# ESP-WiFi.net
KiCad netlist of a schematic drawn in Altium Designer
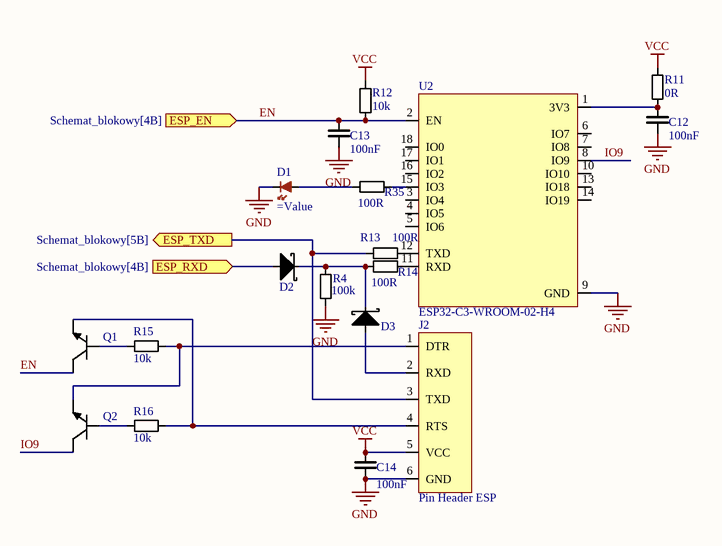
[diagram p0: ESP-WiFi.SchDoc]

(export (version "E")
  (design (tool "Eeschema 10.0.6"))
  (components
    (comp (ref "C12")
      (value "100nF")
      (footprint "0603_CAP")
      (description "Ceramic capacitor")
      (libsource (lib "Cap") (part "Cap"))
    )
    (comp (ref "C13")
      (value "100nF")
      (footprint "0603_CAP")
      (description "Ceramic capacitor")
      (libsource (lib "Cap") (part "Cap"))
    )
    (comp (ref "C14")
      (value "100nF")
      (footprint "0603_CAP")
      (description "Ceramic capacitor")
      (libsource (lib "Cap") (part "Cap"))
    )
    (comp (ref "D1")
      (value "~")
      (footprint "0603_LED_R_Reflow")
      (description "Red LED diode")
      (fields (field (name "PARTNUMBER") "APT1608SURC"))
      (libsource (lib "PBL4_GR4_SchLib") (part "LED_R_small"))
    )
    (comp (ref "D2")
      (value "~")
      (footprint "SOT23-R")
      (description "Schottky Diode")
      (fields (field (name "PARTNUMBER") "BAT54C"))
      (libsource (lib "Diodes") (part "D Schottky"))
    )
    (comp (ref "D3")
      (value "~")
      (footprint "SOT23-R")
      (description "Schottky Diode")
      (fields (field (name "PARTNUMBER") "BAT54C"))
      (libsource (lib "Diodes") (part "D Schottky"))
    )
    (comp (ref "J2")
      (value "Pin Header ESP")
      (footprint "SAMTEC_TSW-112-16-T-S-06")
      (libsource (lib "ESP32-C3-WROOM-02-H4") (part "Pin Header ESP"))
    )
    (comp (ref "Q1")
      (value "NPN")
      (footprint "SOT95P240X110-3N")
      (description "NPN General-purpose Transistor")
      (fields (field (name "PARTNUMBER") "BC848C-7-F"))
      (libsource (lib "NPN") (part "NPN"))
    )
    (comp (ref "Q2")
      (value "NPN")
      (footprint "SOT95P240X110-3N")
      (description "NPN General-purpose Transistor")
      (fields (field (name "PARTNUMBER") "BC848C-7-F"))
      (libsource (lib "NPN") (part "NPN"))
    )
    (comp (ref "R4")
      (value "100k")
      (footprint "0603_RES")
      (description "Resistor")
      (libsource (lib "RES") (part "RES"))
    )
    (comp (ref "R11")
      (value "0R")
      (footprint "0603_RES")
      (description "Resistor")
      (libsource (lib "RES") (part "RES"))
    )
    (comp (ref "R12")
      (value "10k")
      (footprint "0603_RES")
      (description "Resistor")
      (libsource (lib "RES") (part "RES"))
    )
    (comp (ref "R13")
      (value "100R")
      (footprint "0603_RES")
      (description "Resistor")
      (libsource (lib "RES") (part "RES"))
    )
    (comp (ref "R14")
      (value "100R")
      (footprint "0603_RES")
      (description "Resistor")
      (libsource (lib "RES") (part "RES"))
    )
    (comp (ref "R15")
      (value "10k")
      (footprint "0603_RES")
      (description "Resistor")
      (libsource (lib "RES") (part "RES"))
    )
    (comp (ref "R16")
      (value "10k")
      (footprint "0603_RES")
      (description "Resistor")
      (libsource (lib "RES") (part "RES"))
    )
    (comp (ref "R35")
      (value "100R")
      (footprint "0603_RES")
      (description "Resistor")
      (libsource (lib "RES") (part "RES"))
    )
    (comp (ref "U2")
      (value "ESP32-C3-WROOM-02-H4")
      (footprint "MODULE_ESP32-C3-WROOM-02-H4")
      (fields (field (name "MF") "Espressif Systems"))
      (libsource (lib "ESP32-C3-WROOM-02-H4") (part "ESP32-C3-WROOM-02-H4"))
    )
  )
  (nets
    (net (code "1") (name "/EN") (class "Default")
      (node (ref "C13") (pin "2") (pinfunction "2_2") (pintype "passive"))
      (node (ref "Q1") (pin "3") (pinfunction "C_3") (pintype "passive"))
      (node (ref "R12") (pin "1") (pinfunction "1_1") (pintype "passive"))
      (node (ref "U2") (pin "2") (pinfunction "EN_2") (pintype "passive"))
    )
    (net (code "2") (name "/ESP_RXD") (class "Default")
      (node (ref "D2") (pin "1") (pinfunction "A_1") (pintype "passive"))
    )
    (net (code "3") (name "/ESP_TXD") (class "Default")
      (node (ref "J2") (pin "3") (pinfunction "TXD_3") (pintype "passive"))
      (node (ref "R13") (pin "1") (pinfunction "1_1") (pintype "passive"))
    )
    (net (code "4") (name "/IO9") (class "Default")
      (node (ref "Q2") (pin "3") (pinfunction "C_3") (pintype "passive"))
      (node (ref "U2") (pin "8") (pinfunction "IO9_8") (pintype "passive"))
    )
    (net (code "5") (name "GND") (class "Default")
      (node (ref "C12") (pin "1") (pinfunction "1_1") (pintype "passive"))
      (node (ref "C13") (pin "1") (pinfunction "1_1") (pintype "passive"))
      (node (ref "C14") (pin "1") (pinfunction "1_1") (pintype "passive"))
      (node (ref "D1") (pin "2") (pinfunction "K_2") (pintype "passive"))
      (node (ref "J2") (pin "6") (pinfunction "GND_6") (pintype "passive"))
      (node (ref "R4") (pin "1") (pinfunction "1_1") (pintype "passive"))
      (node (ref "U2") (pin "9") (pinfunction "GND_9") (pintype "passive"))
    )
    (net (code "6") (name "Net-(D1-A)") (class "Default")
      (node (ref "D1") (pin "1") (pinfunction "A_1") (pintype "passive"))
      (node (ref "R35") (pin "1") (pinfunction "1_1") (pintype "passive"))
    )
    (net (code "7") (name "Net-(D2-K)") (class "Default")
      (node (ref "D2") (pin "3") (pinfunction "K_3") (pintype "passive"))
      (node (ref "D3") (pin "3") (pinfunction "K_3") (pintype "passive"))
      (node (ref "R14") (pin "1") (pinfunction "1_1") (pintype "passive"))
      (node (ref "R4") (pin "2") (pinfunction "2_2") (pintype "passive"))
    )
    (net (code "8") (name "Net-(D3-A)") (class "Default")
      (node (ref "D3") (pin "1") (pinfunction "A_1") (pintype "passive"))
      (node (ref "J2") (pin "2") (pinfunction "RXD_2") (pintype "passive"))
    )
    (net (code "9") (name "Net-(J2-DTR)") (class "Default")
      (node (ref "J2") (pin "1") (pinfunction "DTR_1") (pintype "passive"))
      (node (ref "Q2") (pin "2") (pinfunction "E_2") (pintype "passive"))
      (node (ref "R15") (pin "1") (pinfunction "1_1") (pintype "passive"))
    )
    (net (code "10") (name "Net-(J2-RTS)") (class "Default")
      (node (ref "J2") (pin "4") (pinfunction "RTS_4") (pintype "passive"))
      (node (ref "Q1") (pin "2") (pinfunction "E_2") (pintype "passive"))
      (node (ref "R16") (pin "1") (pinfunction "1_1") (pintype "passive"))
    )
    (net (code "11") (name "Net-(Q1-B)") (class "Default")
      (node (ref "Q1") (pin "1") (pinfunction "B_1") (pintype "passive"))
      (node (ref "R15") (pin "2") (pinfunction "2_2") (pintype "passive"))
    )
    (net (code "12") (name "Net-(Q2-B)") (class "Default")
      (node (ref "Q2") (pin "1") (pinfunction "B_1") (pintype "passive"))
      (node (ref "R16") (pin "2") (pinfunction "2_2") (pintype "passive"))
    )
    (net (code "13") (name "Net-(U2-3V3)") (class "Default")
      (node (ref "C12") (pin "2") (pinfunction "2_2") (pintype "passive"))
      (node (ref "R11") (pin "1") (pinfunction "1_1") (pintype "passive"))
      (node (ref "U2") (pin "1") (pinfunction "3V3_1") (pintype "passive"))
    )
    (net (code "14") (name "Net-(U2-IO3)") (class "Default")
      (node (ref "R35") (pin "2") (pinfunction "2_2") (pintype "passive"))
      (node (ref "U2") (pin "15") (pinfunction "IO3_15") (pintype "passive"))
    )
    (net (code "15") (name "Net-(U2-RXD)") (class "Default")
      (node (ref "R14") (pin "2") (pinfunction "2_2") (pintype "passive"))
      (node (ref "U2") (pin "11") (pinfunction "RXD_11") (pintype "passive"))
    )
    (net (code "16") (name "Net-(U2-TXD)") (class "Default")
      (node (ref "R13") (pin "2") (pinfunction "2_2") (pintype "passive"))
      (node (ref "U2") (pin "12") (pinfunction "TXD_12") (pintype "passive"))
    )
    (net (code "17") (name "VCC") (class "Default")
      (node (ref "C14") (pin "2") (pinfunction "2_2") (pintype "passive"))
      (node (ref "J2") (pin "5") (pinfunction "VCC_5") (pintype "passive"))
      (node (ref "R11") (pin "2") (pinfunction "2_2") (pintype "passive"))
      (node (ref "R12") (pin "2") (pinfunction "2_2") (pintype "passive"))
    )
    (net (code "18") (name "unconnected-(U2-IO0-Pad18)") (class "Default")
      (node (ref "U2") (pin "18") (pinfunction "IO0_18") (pintype "passive"))
    )
    (net (code "19") (name "unconnected-(U2-IO1-Pad17)") (class "Default")
      (node (ref "U2") (pin "17") (pinfunction "IO1_17") (pintype "passive"))
    )
    (net (code "20") (name "unconnected-(U2-IO2-Pad16)") (class "Default")
      (node (ref "U2") (pin "16") (pinfunction "IO2_16") (pintype "passive"))
    )
    (net (code "21") (name "unconnected-(U2-IO4-Pad3)") (class "Default")
      (node (ref "U2") (pin "3") (pinfunction "IO4_3") (pintype "passive"))
    )
    (net (code "22") (name "unconnected-(U2-IO5-Pad4)") (class "Default")
      (node (ref "U2") (pin "4") (pinfunction "IO5_4") (pintype "passive"))
    )
    (net (code "23") (name "unconnected-(U2-IO6-Pad5)") (class "Default")
      (node (ref "U2") (pin "5") (pinfunction "IO6_5") (pintype "passive"))
    )
    (net (code "24") (name "unconnected-(U2-IO7-Pad6)") (class "Default")
      (node (ref "U2") (pin "6") (pinfunction "IO7_6") (pintype "passive"))
    )
    (net (code "25") (name "unconnected-(U2-IO8-Pad7)") (class "Default")
      (node (ref "U2") (pin "7") (pinfunction "IO8_7") (pintype "passive"))
    )
    (net (code "26") (name "unconnected-(U2-IO10-Pad10)") (class "Default")
      (node (ref "U2") (pin "10") (pinfunction "IO10_10") (pintype "passive"))
    )
    (net (code "27") (name "unconnected-(U2-IO18-Pad13)") (class "Default")
      (node (ref "U2") (pin "13") (pinfunction "IO18_13") (pintype "passive"))
    )
    (net (code "28") (name "unconnected-(U2-IO19-Pad14)") (class "Default")
      (node (ref "U2") (pin "14") (pinfunction "IO19_14") (pintype "passive"))
    )
  )
)
